# pwm_generator.net
KiCad netlist of a schematic drawn in Altium Designer
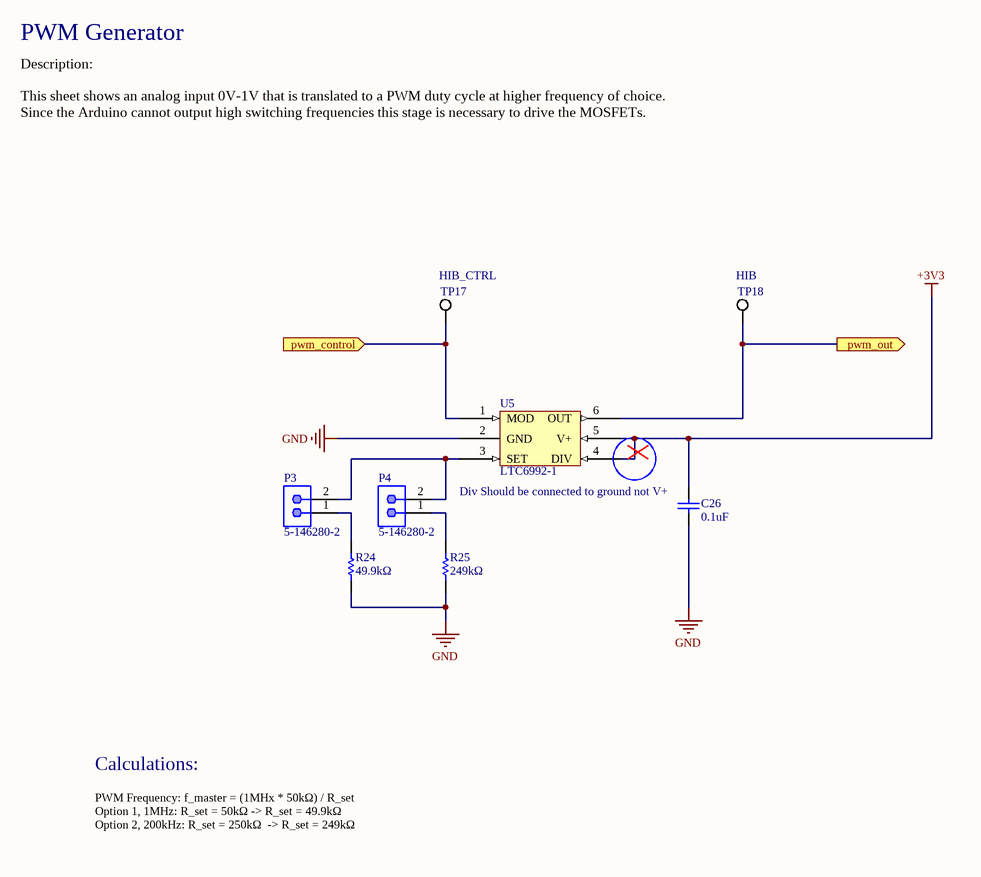
[diagram p0: pwm_generator.SchDoc]

(export (version "E")
  (design (tool "Eeschema 10.0.6"))
  (components
    (comp (ref "C26")
      (value "0.1uF")
      (footprint "CAPC1608X90X35ML10T15")
      (fields
        (field (name "TOLERANCE") "10%")
        (field (name "VOLTAGE") "50V")
        (field (name "MANUFACTURER") "Murata")
      )
      (libsource (lib "Altium Content Vault") (part "CAP-NP-2"))
    )
    (comp (ref "P3")
      (value "5-146280-2")
      (footprint "TECO-5-146280-2_V")
      (fields (field (name "MANUFACTURER") "TE Connectivity"))
      (libsource (lib "Altium Content Vault") (part "CN-1P-M-R2"))
    )
    (comp (ref "P4")
      (value "5-146280-2")
      (footprint "TECO-5-146280-2_V")
      (fields (field (name "MANUFACTURER") "TE Connectivity"))
      (libsource (lib "Altium Content Vault") (part "CN-1P-M-R2"))
    )
    (comp (ref "R24")
      (value "49.9kΩ")
      (footprint "RESC1609X55X30ML10T20")
      (description "TNPW060349K9BEEN")
      (fields (field (name "MANUFACTURER") "Vishay Dale"))
      (libsource (lib "Altium Content Vault") (part "RES"))
    )
    (comp (ref "R25")
      (value "249kΩ")
      (footprint "RESC1609X55X30LL10T20")
      (description "TNPW0603249KBEEA")
      (fields (field (name "MANUFACTURER") "Vishay Dale"))
      (libsource (lib "Altium Content Vault") (part "RES"))
    )
    (comp (ref "TP17")
      (value "HIB_CTRL")
      (footprint "KSTN-5012_V")
      (description "Test Point, White, Through Hole, RoHS, Bulk")
      (fields (field (name "MANUFACTURER") "Keystone"))
      (libsource (lib "Altium Content Vault") (part "TESTPOINT_WHITE"))
    )
    (comp (ref "TP18")
      (value "HIB")
      (footprint "KSTN-5012_V")
      (description "Test Point, White, Through Hole, RoHS, Bulk")
      (fields (field (name "MANUFACTURER") "Keystone"))
      (libsource (lib "Altium Content Vault") (part "TESTPOINT_WHITE"))
    )
    (comp (ref "U5")
      (value "LTC6992-1")
      (footprint "LT-S6-6-TSOT-23_L")
      (description "Oscillator, Silicon IC 3.81Hz ~ 1MHz TSOT-23-6")
      (libsource (lib "digital_power") (part "LTC6992-1"))
    )
  )
  (nets
    (net (code "1") (name "+3V3") (class "Default")
      (node (ref "C26") (pin "2") (pinfunction "2_2") (pintype "passive"))
      (node (ref "U5") (pin "4") (pinfunction "DIV_4") (pintype "input"))
      (node (ref "U5") (pin "5") (pinfunction "V+_5") (pintype "input"))
    )
    (net (code "2") (name "/pwm_control") (class "Default")
      (node (ref "TP17") (pin "1") (pinfunction "1_1") (pintype "passive"))
      (node (ref "U5") (pin "1") (pinfunction "MOD_1") (pintype "input"))
    )
    (net (code "3") (name "/pwm_out") (class "Default")
      (node (ref "TP18") (pin "1") (pinfunction "1_1") (pintype "passive"))
      (node (ref "U5") (pin "6") (pinfunction "OUT_6") (pintype "output"))
    )
    (net (code "4") (name "GND") (class "Default")
      (node (ref "C26") (pin "1") (pinfunction "1_1") (pintype "passive"))
      (node (ref "R24") (pin "1") (pinfunction "1_1") (pintype "passive"))
      (node (ref "R25") (pin "1") (pinfunction "1_1") (pintype "passive"))
      (node (ref "U5") (pin "2") (pinfunction "GND_2") (pintype "power_in"))
    )
    (net (code "5") (name "Net-(P3-Pad1)") (class "Default")
      (node (ref "P3") (pin "1") (pinfunction "1_1") (pintype "passive"))
      (node (ref "R24") (pin "2") (pinfunction "2_2") (pintype "passive"))
    )
    (net (code "6") (name "Net-(P4-Pad1)") (class "Default")
      (node (ref "P4") (pin "1") (pinfunction "1_1") (pintype "passive"))
      (node (ref "R25") (pin "2") (pinfunction "2_2") (pintype "passive"))
    )
    (net (code "7") (name "Net-(U5-SET)") (class "Default")
      (node (ref "P3") (pin "2") (pinfunction "2_2") (pintype "passive"))
      (node (ref "P4") (pin "2") (pinfunction "2_2") (pintype "passive"))
      (node (ref "U5") (pin "3") (pinfunction "SET_3") (pintype "input"))
    )
  )
)
